# Regulator.net
KiCad netlist of a schematic drawn in EAGLE
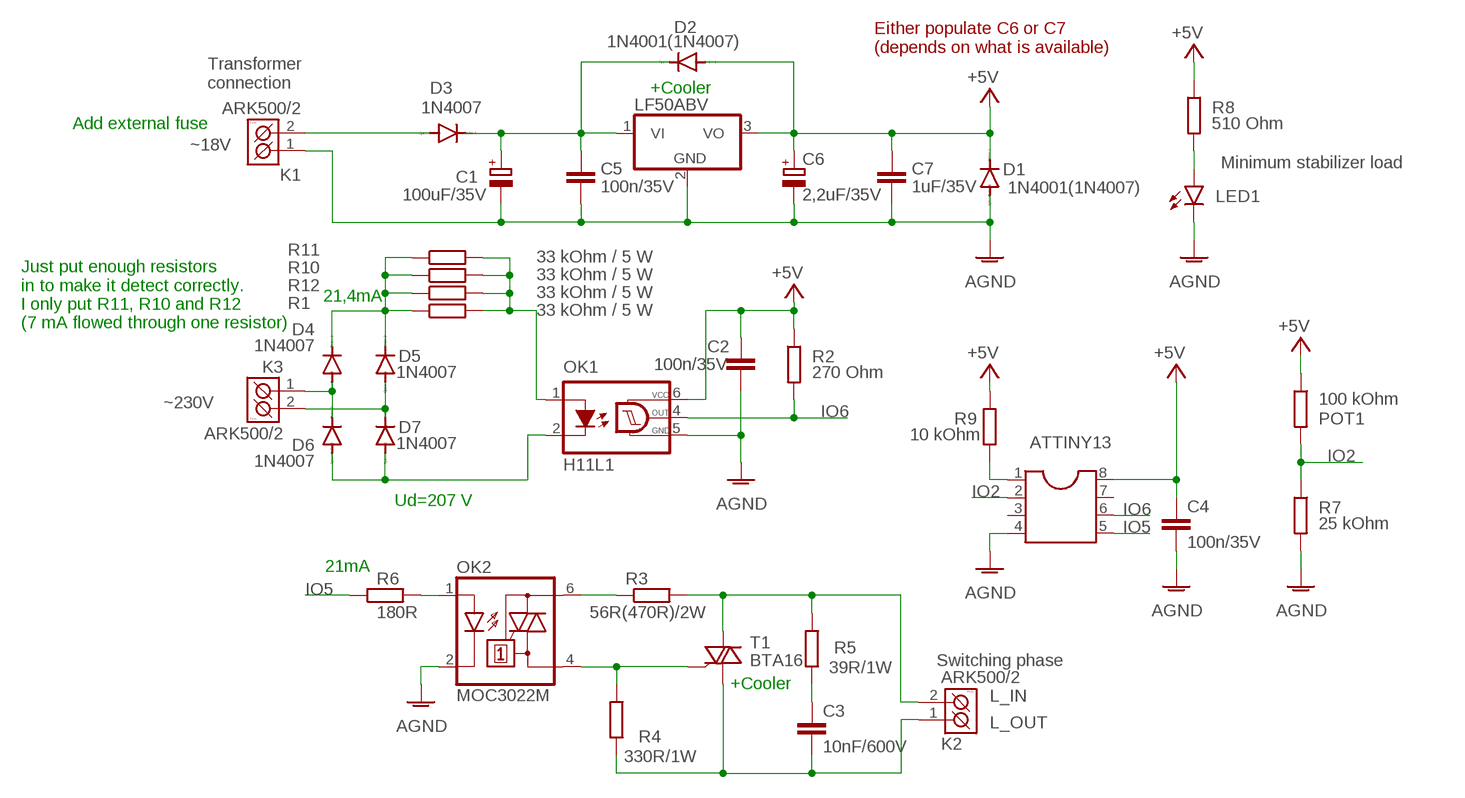
[diagram p0: schematic, sheet 1]

(export (version "E")
  (design (tool "Eeschema 10.0.6"))
  (components
    (comp (ref "ATTINY13")
      (value "DIL8S")
      (footprint "eagle-import:SOCKET-08")
      (libsource (lib "eagle-import") (part "DIL8S"))
    )
    (comp (ref "C1")
      (value "100uF/35V")
      (footprint "eagle-import:E3,5-8")
      (libsource (lib "eagle-import") (part "CPOL-EUE3.5-8"))
    )
    (comp (ref "C2")
      (value "100n/35V")
      (footprint "eagle-import:C050-025X075")
      (libsource (lib "eagle-import") (part "C-EU050-025X075"))
    )
    (comp (ref "C3")
      (value "10nF/600V")
      (footprint "eagle-import:C025-030X050")
      (libsource (lib "eagle-import") (part "C-EU025-030X050"))
    )
    (comp (ref "C4")
      (value "100n/35V")
      (footprint "eagle-import:C050-025X075")
      (libsource (lib "eagle-import") (part "C-EU050-025X075"))
    )
    (comp (ref "C5")
      (value "100n/35V")
      (footprint "eagle-import:C050-025X075")
      (libsource (lib "eagle-import") (part "C-EU050-025X075"))
    )
    (comp (ref "C6")
      (value "2,2uF/35V")
      (footprint "eagle-import:E2-4")
      (libsource (lib "eagle-import") (part "CPOL-EUE2-4"))
    )
    (comp (ref "C7")
      (value "1uF/35V")
      (footprint "eagle-import:C050-025X075")
      (libsource (lib "eagle-import") (part "C-EU050-025X075"))
    )
    (comp (ref "D1")
      (value "1N4001(1N4007)")
      (footprint "eagle-import:DO41-7.6")
      (libsource (lib "eagle-import") (part "DIODE-DO41-7.6"))
    )
    (comp (ref "D2")
      (value "1N4001(1N4007)")
      (footprint "eagle-import:DO41-7.6")
      (libsource (lib "eagle-import") (part "DIODE-DO41-7.6"))
    )
    (comp (ref "D3")
      (value "1N4007")
      (footprint "eagle-import:DO41-7.6")
      (libsource (lib "eagle-import") (part "DIODE-DO41-7.6"))
    )
    (comp (ref "D4")
      (value "1N4007")
      (footprint "eagle-import:DO41-7.6")
      (libsource (lib "eagle-import") (part "DIODE-DO41-7.6"))
    )
    (comp (ref "D5")
      (value "1N4007")
      (footprint "eagle-import:DO41-7.6")
      (libsource (lib "eagle-import") (part "DIODE-DO41-7.6"))
    )
    (comp (ref "D6")
      (value "1N4007")
      (footprint "eagle-import:DO41-7.6")
      (libsource (lib "eagle-import") (part "DIODE-DO41-7.6"))
    )
    (comp (ref "D7")
      (value "1N4007")
      (footprint "eagle-import:DO41-7.6")
      (libsource (lib "eagle-import") (part "DIODE-DO41-7.6"))
    )
    (comp (ref "K1")
      (value "ARK500/2")
      (footprint "eagle-import:ARK500_2")
      (libsource (lib "eagle-import") (part "ARK500/2"))
    )
    (comp (ref "K2")
      (value "ARK500/2")
      (footprint "eagle-import:ARK500_2")
      (libsource (lib "eagle-import") (part "ARK500/2"))
    )
    (comp (ref "K3")
      (value "ARK500/2")
      (footprint "eagle-import:ARK500_2")
      (libsource (lib "eagle-import") (part "ARK500/2"))
    )
    (comp (ref "LED1")
      (value "LED5MM")
      (footprint "eagle-import:LED5MM")
      (libsource (lib "eagle-import") (part "LED5MM"))
    )
    (comp (ref "OK1")
      (value "H11L1")
      (footprint "eagle-import:DIL06")
      (fields (field (name "MF") "FAIRCHILD SEMICONDUCTOR") (field (name "MPN") "H11L1-M"))
      (libsource (lib "eagle-import") (part "H11LM1"))
    )
    (comp (ref "OK2")
      (value "MOC3022M")
      (footprint "eagle-import:DIL06")
      (fields (field (name "MF") "FAIRCHILD SEMICONDUCTOR") (field (name "MPN") "MOC3022-M"))
      (libsource (lib "eagle-import") (part "MOC30M22"))
    )
    (comp (ref "POT1")
      (value "100 kOhm")
      (footprint "eagle-import:0207_10")
      (libsource (lib "eagle-import") (part "R-EU_0207/10"))
    )
    (comp (ref "R1")
      (value "33 kOhm / 5 W")
      (footprint "eagle-import:0617V")
      (libsource (lib "eagle-import") (part "R-EU_0617/5V"))
    )
    (comp (ref "R2")
      (value "270 Ohm")
      (footprint "eagle-import:0207_10")
      (libsource (lib "eagle-import") (part "R-EU_0207/10"))
    )
    (comp (ref "R3")
      (value "56R(470R)/2W")
      (footprint "eagle-import:0411_15")
      (libsource (lib "eagle-import") (part "R-EU_0411/15"))
    )
    (comp (ref "R4")
      (value "330R/1W")
      (footprint "eagle-import:0411_15")
      (libsource (lib "eagle-import") (part "R-EU_0411/15"))
    )
    (comp (ref "R5")
      (value "39R/1W")
      (footprint "eagle-import:0411_15")
      (libsource (lib "eagle-import") (part "R-EU_0411/15"))
    )
    (comp (ref "R6")
      (value "180R")
      (footprint "eagle-import:0207_10")
      (libsource (lib "eagle-import") (part "R-EU_0207/10"))
    )
    (comp (ref "R7")
      (value "25 kOhm")
      (footprint "eagle-import:0207_10")
      (libsource (lib "eagle-import") (part "R-EU_0207/10"))
    )
    (comp (ref "R8")
      (value "510 Ohm")
      (footprint "eagle-import:0207_10")
      (libsource (lib "eagle-import") (part "R-EU_0207/10"))
    )
    (comp (ref "R9")
      (value "10 kOhm")
      (footprint "eagle-import:0207_10")
      (libsource (lib "eagle-import") (part "R-EU_0207/10"))
    )
    (comp (ref "R10")
      (value "33 kOhm / 5 W")
      (footprint "eagle-import:0617V")
      (libsource (lib "eagle-import") (part "R-EU_0617/5V"))
    )
    (comp (ref "R11")
      (value "33 kOhm / 5 W")
      (footprint "eagle-import:0617V")
      (libsource (lib "eagle-import") (part "R-EU_0617/5V"))
    )
    (comp (ref "R12")
      (value "33 kOhm / 5 W")
      (footprint "eagle-import:0617V")
      (libsource (lib "eagle-import") (part "R-EU_0617/5V"))
    )
    (comp (ref "ST1")
      (value "LF50ABV")
      (footprint "eagle-import:TO220V")
      (libsource (lib "eagle-import") (part "78TV05"))
    )
    (comp (ref "T1")
      (value "BTA16")
      (footprint "eagle-import:TO220BV")
      (libsource (lib "eagle-import") (part "BT138-V"))
    )
  )
  (nets
    (net (code "1") (name "+5V") (class "Default")
      (node (ref "ATTINY13") (pin "8") (pinfunction "8_8") (pintype "passive"))
      (node (ref "C2") (pin "1") (pinfunction "1_1") (pintype "passive"))
      (node (ref "C4") (pin "1") (pinfunction "1_1") (pintype "passive"))
      (node (ref "C6") (pin "+") (pinfunction "+_+") (pintype "passive"))
      (node (ref "C7") (pin "1") (pinfunction "1_1") (pintype "passive"))
      (node (ref "D1") (pin "C") (pinfunction "C_C") (pintype "passive"))
      (node (ref "D2") (pin "A") (pinfunction "A_A") (pintype "passive"))
      (node (ref "OK1") (pin "6") (pinfunction "VCC_6") (pintype "power_in"))
      (node (ref "POT1") (pin "1") (pinfunction "1_1") (pintype "passive"))
      (node (ref "R2") (pin "1") (pinfunction "1_1") (pintype "passive"))
      (node (ref "R8") (pin "1") (pinfunction "1_1") (pintype "passive"))
      (node (ref "R9") (pin "1") (pinfunction "1_1") (pintype "passive"))
      (node (ref "ST1") (pin "3") (pinfunction "VO_3") (pintype "passive"))
    )
    (net (code "2") (name "/IO2") (class "Default")
      (node (ref "ATTINY13") (pin "2") (pinfunction "2_2") (pintype "passive"))
      (node (ref "POT1") (pin "2") (pinfunction "2_2") (pintype "passive"))
      (node (ref "R7") (pin "1") (pinfunction "1_1") (pintype "passive"))
    )
    (net (code "3") (name "/IO5") (class "Default")
      (node (ref "ATTINY13") (pin "5") (pinfunction "5_5") (pintype "passive"))
      (node (ref "R6") (pin "1") (pinfunction "1_1") (pintype "passive"))
    )
    (net (code "4") (name "/IO6") (class "Default")
      (node (ref "ATTINY13") (pin "6") (pinfunction "6_6") (pintype "passive"))
      (node (ref "OK1") (pin "4") (pinfunction "OUT_4") (pintype "output"))
      (node (ref "R2") (pin "2") (pinfunction "2_2") (pintype "passive"))
    )
    (net (code "5") (name "AGND") (class "Default")
      (node (ref "ATTINY13") (pin "4") (pinfunction "4_4") (pintype "passive"))
      (node (ref "C1") (pin "-") (pinfunction "-_-") (pintype "passive"))
      (node (ref "C2") (pin "2") (pinfunction "2_2") (pintype "passive"))
      (node (ref "C4") (pin "2") (pinfunction "2_2") (pintype "passive"))
      (node (ref "C5") (pin "2") (pinfunction "2_2") (pintype "passive"))
      (node (ref "C6") (pin "-") (pinfunction "-_-") (pintype "passive"))
      (node (ref "C7") (pin "2") (pinfunction "2_2") (pintype "passive"))
      (node (ref "D1") (pin "A") (pinfunction "A_A") (pintype "passive"))
      (node (ref "K1") (pin "1") (pinfunction "K1_1") (pintype "passive"))
      (node (ref "LED1") (pin "K") (pinfunction "C_K") (pintype "passive"))
      (node (ref "OK1") (pin "5") (pinfunction "GND_5") (pintype "power_in"))
      (node (ref "OK2") (pin "2") (pinfunction "C_2") (pintype "passive"))
      (node (ref "R7") (pin "2") (pinfunction "2_2") (pintype "passive"))
      (node (ref "ST1") (pin "2") (pinfunction "GND_2") (pintype "passive"))
    )
    (net (code "6") (name "Net-(ATTINY13-Pad1)") (class "Default")
      (node (ref "ATTINY13") (pin "1") (pinfunction "1_1") (pintype "passive"))
      (node (ref "R9") (pin "2") (pinfunction "2_2") (pintype "passive"))
    )
    (net (code "7") (name "Net-(C3-Pad1)") (class "Default")
      (node (ref "C3") (pin "1") (pinfunction "1_1") (pintype "passive"))
      (node (ref "R5") (pin "1") (pinfunction "1_1") (pintype "passive"))
    )
    (net (code "8") (name "Net-(D4-PadC)") (class "Default")
      (node (ref "D4") (pin "C") (pinfunction "C_C") (pintype "passive"))
      (node (ref "D5") (pin "C") (pinfunction "C_C") (pintype "passive"))
      (node (ref "R1") (pin "1") (pinfunction "1_1") (pintype "passive"))
      (node (ref "R10") (pin "1") (pinfunction "1_1") (pintype "passive"))
      (node (ref "R11") (pin "1") (pinfunction "1_1") (pintype "passive"))
      (node (ref "R12") (pin "1") (pinfunction "1_1") (pintype "passive"))
    )
    (net (code "9") (name "Net-(K1-K2)") (class "Default")
      (node (ref "D3") (pin "A") (pinfunction "A_A") (pintype "passive"))
      (node (ref "K1") (pin "2") (pinfunction "K2_2") (pintype "passive"))
    )
    (net (code "10") (name "Net-(K2-K1)") (class "Default")
      (node (ref "C3") (pin "2") (pinfunction "2_2") (pintype "passive"))
      (node (ref "K2") (pin "1") (pinfunction "K1_1") (pintype "passive"))
      (node (ref "R4") (pin "1") (pinfunction "1_1") (pintype "passive"))
      (node (ref "T1") (pin "T1") (pinfunction "A1_T1") (pintype "passive"))
    )
    (net (code "11") (name "Net-(K2-K2)") (class "Default")
      (node (ref "K2") (pin "2") (pinfunction "K2_2") (pintype "passive"))
      (node (ref "R3") (pin "2") (pinfunction "2_2") (pintype "passive"))
      (node (ref "R5") (pin "2") (pinfunction "2_2") (pintype "passive"))
      (node (ref "T1") (pin "T2") (pinfunction "A2_T2") (pintype "passive"))
    )
    (net (code "12") (name "Net-(K3-K1)") (class "Default")
      (node (ref "D4") (pin "A") (pinfunction "A_A") (pintype "passive"))
      (node (ref "D6") (pin "C") (pinfunction "C_C") (pintype "passive"))
      (node (ref "K3") (pin "1") (pinfunction "K1_1") (pintype "passive"))
    )
    (net (code "13") (name "Net-(K3-K2)") (class "Default")
      (node (ref "D5") (pin "A") (pinfunction "A_A") (pintype "passive"))
      (node (ref "D7") (pin "C") (pinfunction "C_C") (pintype "passive"))
      (node (ref "K3") (pin "2") (pinfunction "K2_2") (pintype "passive"))
    )
    (net (code "14") (name "Net-(LED1-PadA)") (class "Default")
      (node (ref "LED1") (pin "A") (pinfunction "A_A") (pintype "passive"))
      (node (ref "R8") (pin "2") (pinfunction "2_2") (pintype "passive"))
    )
    (net (code "15") (name "Net-(OK1-A)") (class "Default")
      (node (ref "OK1") (pin "1") (pinfunction "A_1") (pintype "passive"))
      (node (ref "R1") (pin "2") (pinfunction "2_2") (pintype "passive"))
      (node (ref "R10") (pin "2") (pinfunction "2_2") (pintype "passive"))
      (node (ref "R11") (pin "2") (pinfunction "2_2") (pintype "passive"))
      (node (ref "R12") (pin "2") (pinfunction "2_2") (pintype "passive"))
    )
    (net (code "16") (name "Net-(OK1-C)") (class "Default")
      (node (ref "D6") (pin "A") (pinfunction "A_A") (pintype "passive"))
      (node (ref "D7") (pin "A") (pinfunction "A_A") (pintype "passive"))
      (node (ref "OK1") (pin "2") (pinfunction "C_2") (pintype "passive"))
    )
    (net (code "17") (name "Net-(OK2-A)") (class "Default")
      (node (ref "OK2") (pin "1") (pinfunction "A_1") (pintype "passive"))
      (node (ref "R6") (pin "2") (pinfunction "2_2") (pintype "passive"))
    )
    (net (code "18") (name "Net-(OK2-A1)") (class "Default")
      (node (ref "OK2") (pin "4") (pinfunction "A1_4") (pintype "passive"))
      (node (ref "R4") (pin "2") (pinfunction "2_2") (pintype "passive"))
      (node (ref "T1") (pin "G") (pinfunction "G_G") (pintype "passive"))
    )
    (net (code "19") (name "Net-(OK2-A2)") (class "Default")
      (node (ref "OK2") (pin "6") (pinfunction "A2_6") (pintype "passive"))
      (node (ref "R3") (pin "1") (pinfunction "1_1") (pintype "passive"))
    )
    (net (code "20") (name "Net-(ST1-VI)") (class "Default")
      (node (ref "C1") (pin "+") (pinfunction "+_+") (pintype "passive"))
      (node (ref "C5") (pin "1") (pinfunction "1_1") (pintype "passive"))
      (node (ref "D2") (pin "C") (pinfunction "C_C") (pintype "passive"))
      (node (ref "D3") (pin "C") (pinfunction "C_C") (pintype "passive"))
      (node (ref "ST1") (pin "1") (pinfunction "VI_1") (pintype "input"))
    )
    (net (code "21") (name "unconnected-(ATTINY13-Pad3)") (class "Default")
      (node (ref "ATTINY13") (pin "3") (pinfunction "3_3") (pintype "passive"))
    )
    (net (code "22") (name "unconnected-(ATTINY13-Pad7)") (class "Default")
      (node (ref "ATTINY13") (pin "7") (pinfunction "7_7") (pintype "passive"))
    )
  )
)
